# breakout.net
KiCad netlist of a schematic drawn in EAGLE
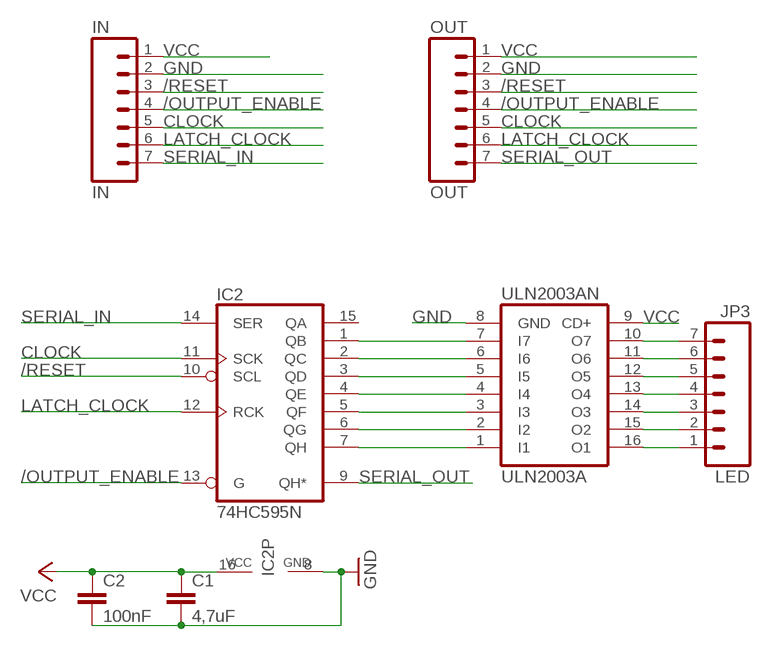
[diagram p0: schematic, sheet 1]

(export (version "E")
  (design (tool "Eeschema 10.0.6"))
  (components
    (comp (ref "C1")
      (value "4,7uF")
      (footprint "eagle-import:C025-024X044")
      (libsource (lib "eagle-import") (part "C-EU025-024X044"))
    )
    (comp (ref "C2")
      (value "100nF")
      (footprint "eagle-import:C025-024X044")
      (libsource (lib "eagle-import") (part "C-EU025-024X044"))
    )
    (comp (ref "IC2")
      (value "74HC595N")
      (footprint "eagle-import:DIL16")
      (libsource (lib "eagle-import") (part "74595NHC"))
    )
    (comp (ref "IN")
      (value "IN")
      (footprint "eagle-import:1X07")
      (libsource (lib "eagle-import") (part "M07"))
    )
    (comp (ref "JP3")
      (value "LED")
      (footprint "eagle-import:1X07")
      (libsource (lib "eagle-import") (part "M07"))
    )
    (comp (ref "OUT")
      (value "OUT")
      (footprint "eagle-import:1X07")
      (libsource (lib "eagle-import") (part "M07"))
    )
    (comp (ref "ULN2003A")
      (value "ULN2003AN")
      (footprint "eagle-import:DIL16")
      (libsource (lib "eagle-import") (part "ULN2003AN"))
    )
  )
  (nets
    (net (code "1") (name "/CLOCK") (class "Default")
      (node (ref "IC2") (pin "11") (pinfunction "SCK_11") (pintype "input"))
      (node (ref "IN") (pin "5") (pinfunction "5_5") (pintype "passive"))
      (node (ref "OUT") (pin "5") (pinfunction "5_5") (pintype "passive"))
    )
    (net (code "2") (name "/LATCH_CLOCK") (class "Default")
      (node (ref "IC2") (pin "12") (pinfunction "RCK_12") (pintype "input"))
      (node (ref "IN") (pin "6") (pinfunction "6_6") (pintype "passive"))
      (node (ref "OUT") (pin "6") (pinfunction "6_6") (pintype "passive"))
    )
    (net (code "3") (name "/SERIAL_IN") (class "Default")
      (node (ref "IC2") (pin "14") (pinfunction "SER_14") (pintype "input"))
      (node (ref "IN") (pin "7") (pinfunction "7_7") (pintype "passive"))
    )
    (net (code "4") (name "/SERIAL_OUT") (class "Default")
      (node (ref "IC2") (pin "9") (pinfunction "QH*_9") (pintype "tri_state"))
      (node (ref "OUT") (pin "7") (pinfunction "7_7") (pintype "passive"))
    )
    (net (code "5") (name "/{slash}OUTPUT_ENABLE") (class "Default")
      (node (ref "IC2") (pin "13") (pinfunction "G_13") (pintype "input"))
      (node (ref "IN") (pin "4") (pinfunction "4_4") (pintype "passive"))
      (node (ref "OUT") (pin "4") (pinfunction "4_4") (pintype "passive"))
    )
    (net (code "6") (name "/{slash}RESET") (class "Default")
      (node (ref "IC2") (pin "10") (pinfunction "SCL_10") (pintype "input"))
      (node (ref "IN") (pin "3") (pinfunction "3_3") (pintype "passive"))
      (node (ref "OUT") (pin "3") (pinfunction "3_3") (pintype "passive"))
    )
    (net (code "7") (name "GND") (class "Default")
      (node (ref "C1") (pin "2") (pinfunction "2_2") (pintype "passive"))
      (node (ref "C2") (pin "2") (pinfunction "2_2") (pintype "passive"))
      (node (ref "IC2") (pin "8") (pinfunction "GND_8") (pintype "power_in"))
      (node (ref "IN") (pin "2") (pinfunction "2_2") (pintype "passive"))
      (node (ref "OUT") (pin "2") (pinfunction "2_2") (pintype "passive"))
      (node (ref "ULN2003A") (pin "8") (pinfunction "GND_8") (pintype "power_in"))
    )
    (net (code "8") (name "Net-(IC2A-QB)") (class "Default")
      (node (ref "IC2") (pin "1") (pinfunction "QB_1") (pintype "tri_state"))
      (node (ref "ULN2003A") (pin "7") (pinfunction "I7_7") (pintype "input"))
    )
    (net (code "9") (name "Net-(IC2A-QC)") (class "Default")
      (node (ref "IC2") (pin "2") (pinfunction "QC_2") (pintype "tri_state"))
      (node (ref "ULN2003A") (pin "6") (pinfunction "I6_6") (pintype "input"))
    )
    (net (code "10") (name "Net-(IC2A-QD)") (class "Default")
      (node (ref "IC2") (pin "3") (pinfunction "QD_3") (pintype "tri_state"))
      (node (ref "ULN2003A") (pin "5") (pinfunction "I5_5") (pintype "input"))
    )
    (net (code "11") (name "Net-(IC2A-QE)") (class "Default")
      (node (ref "IC2") (pin "4") (pinfunction "QE_4") (pintype "tri_state"))
      (node (ref "ULN2003A") (pin "4") (pinfunction "I4_4") (pintype "input"))
    )
    (net (code "12") (name "Net-(IC2A-QF)") (class "Default")
      (node (ref "IC2") (pin "5") (pinfunction "QF_5") (pintype "tri_state"))
      (node (ref "ULN2003A") (pin "3") (pinfunction "I3_3") (pintype "input"))
    )
    (net (code "13") (name "Net-(IC2A-QG)") (class "Default")
      (node (ref "IC2") (pin "6") (pinfunction "QG_6") (pintype "tri_state"))
      (node (ref "ULN2003A") (pin "2") (pinfunction "I2_2") (pintype "input"))
    )
    (net (code "14") (name "Net-(IC2A-QH)") (class "Default")
      (node (ref "IC2") (pin "7") (pinfunction "QH_7") (pintype "tri_state"))
      (node (ref "ULN2003A") (pin "1") (pinfunction "I1_1") (pintype "input"))
    )
    (net (code "15") (name "Net-(ULN2003A-O1)") (class "Default")
      (node (ref "JP3") (pin "1") (pinfunction "1_1") (pintype "passive"))
      (node (ref "ULN2003A") (pin "16") (pinfunction "O1_16") (pintype "open_collector"))
    )
    (net (code "16") (name "Net-(ULN2003A-O2)") (class "Default")
      (node (ref "JP3") (pin "2") (pinfunction "2_2") (pintype "passive"))
      (node (ref "ULN2003A") (pin "15") (pinfunction "O2_15") (pintype "open_collector"))
    )
    (net (code "17") (name "Net-(ULN2003A-O3)") (class "Default")
      (node (ref "JP3") (pin "3") (pinfunction "3_3") (pintype "passive"))
      (node (ref "ULN2003A") (pin "14") (pinfunction "O3_14") (pintype "open_collector"))
    )
    (net (code "18") (name "Net-(ULN2003A-O4)") (class "Default")
      (node (ref "JP3") (pin "4") (pinfunction "4_4") (pintype "passive"))
      (node (ref "ULN2003A") (pin "13") (pinfunction "O4_13") (pintype "open_collector"))
    )
    (net (code "19") (name "Net-(ULN2003A-O5)") (class "Default")
      (node (ref "JP3") (pin "5") (pinfunction "5_5") (pintype "passive"))
      (node (ref "ULN2003A") (pin "12") (pinfunction "O5_12") (pintype "open_collector"))
    )
    (net (code "20") (name "Net-(ULN2003A-O6)") (class "Default")
      (node (ref "JP3") (pin "6") (pinfunction "6_6") (pintype "passive"))
      (node (ref "ULN2003A") (pin "11") (pinfunction "O6_11") (pintype "open_collector"))
    )
    (net (code "21") (name "Net-(ULN2003A-O7)") (class "Default")
      (node (ref "JP3") (pin "7") (pinfunction "7_7") (pintype "passive"))
      (node (ref "ULN2003A") (pin "10") (pinfunction "O7_10") (pintype "open_collector"))
    )
    (net (code "22") (name "VCC") (class "Default")
      (node (ref "C1") (pin "1") (pinfunction "1_1") (pintype "passive"))
      (node (ref "C2") (pin "1") (pinfunction "1_1") (pintype "passive"))
      (node (ref "IC2") (pin "16") (pinfunction "VCC_16") (pintype "power_in"))
      (node (ref "IN") (pin "1") (pinfunction "1_1") (pintype "passive"))
      (node (ref "OUT") (pin "1") (pinfunction "1_1") (pintype "passive"))
      (node (ref "ULN2003A") (pin "9") (pinfunction "CD+_9") (pintype "passive"))
    )
    (net (code "23") (name "unconnected-(IC2A-QA-Pad15)") (class "Default")
      (node (ref "IC2") (pin "15") (pinfunction "QA_15") (pintype "tri_state"))
    )
  )
)
